# IDC_RS50_DIO_Sheet1.net
KiCad netlist of a schematic drawn in Altium Designer
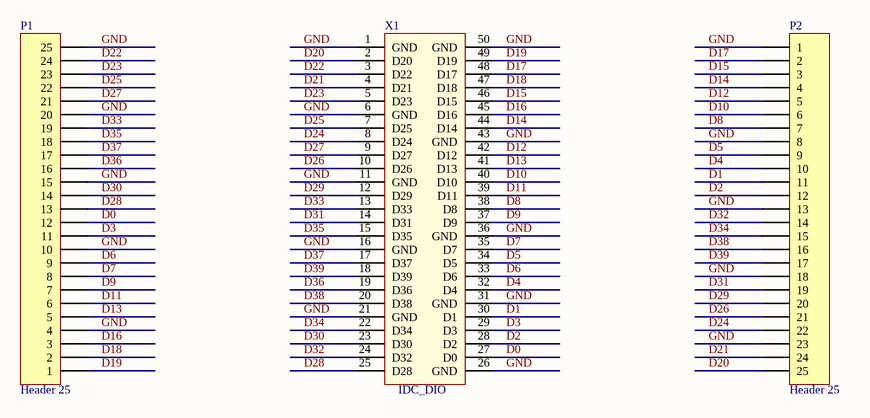
[diagram p0: IDC_RS50_DIO_Sheet1.SchDoc]

(export (version "E")
  (design (tool "Eeschema 10.0.6"))
  (components
    (comp (ref "P1")
      (value "Header 25")
      (footprint "HDR1X25")
      (description "Header, 25-Pin")
      (fields (field (name "PUBLISHER") "Altium Limited"))
      (libsource (lib "") (part "Header 25_1"))
    )
    (comp (ref "P2")
      (value "Header 25")
      (footprint "HDR1X25")
      (description "Header, 25-Pin")
      (fields (field (name "PUBLISHER") "Altium Limited"))
      (libsource (lib "Miscellaneous Connectors") (part "Header 25"))
    )
    (comp (ref "X1") (value "IDC_DIO") (footprint "IDC_DIO") (libsource (lib "VPL") (part "IDC_DIO")))
  )
  (nets
    (net (code "1") (name "/D0") (class "Default")
      (node (ref "P1") (pin "12") (pinfunction "12_12") (pintype "passive"))
      (node (ref "X1") (pin "27") (pinfunction "D0_27") (pintype "passive"))
    )
    (net (code "2") (name "/D1") (class "Default")
      (node (ref "P2") (pin "11") (pinfunction "11_11") (pintype "passive"))
      (node (ref "X1") (pin "30") (pinfunction "D1_30") (pintype "passive"))
    )
    (net (code "3") (name "/D2") (class "Default")
      (node (ref "P2") (pin "12") (pinfunction "12_12") (pintype "passive"))
      (node (ref "X1") (pin "28") (pinfunction "D2_28") (pintype "passive"))
    )
    (net (code "4") (name "/D3") (class "Default")
      (node (ref "P1") (pin "11") (pinfunction "11_11") (pintype "passive"))
      (node (ref "X1") (pin "29") (pinfunction "D3_29") (pintype "passive"))
    )
    (net (code "5") (name "/D4") (class "Default")
      (node (ref "P2") (pin "10") (pinfunction "10_10") (pintype "passive"))
      (node (ref "X1") (pin "32") (pinfunction "D4_32") (pintype "passive"))
    )
    (net (code "6") (name "/D5") (class "Default")
      (node (ref "P2") (pin "9") (pinfunction "9_9") (pintype "passive"))
      (node (ref "X1") (pin "34") (pinfunction "D5_34") (pintype "passive"))
    )
    (net (code "7") (name "/D6") (class "Default")
      (node (ref "P1") (pin "9") (pinfunction "9_9") (pintype "passive"))
      (node (ref "X1") (pin "33") (pinfunction "D6_33") (pintype "passive"))
    )
    (net (code "8") (name "/D7") (class "Default")
      (node (ref "P1") (pin "8") (pinfunction "8_8") (pintype "passive"))
      (node (ref "X1") (pin "35") (pinfunction "D7_35") (pintype "passive"))
    )
    (net (code "9") (name "/D8") (class "Default")
      (node (ref "P2") (pin "7") (pinfunction "7_7") (pintype "passive"))
      (node (ref "X1") (pin "38") (pinfunction "D8_38") (pintype "passive"))
    )
    (net (code "10") (name "/D9") (class "Default")
      (node (ref "P1") (pin "7") (pinfunction "7_7") (pintype "passive"))
      (node (ref "X1") (pin "37") (pinfunction "D9_37") (pintype "passive"))
    )
    (net (code "11") (name "/D10") (class "Default")
      (node (ref "P2") (pin "6") (pinfunction "6_6") (pintype "passive"))
      (node (ref "X1") (pin "40") (pinfunction "D10_40") (pintype "passive"))
    )
    (net (code "12") (name "/D11") (class "Default")
      (node (ref "P1") (pin "6") (pinfunction "6_6") (pintype "passive"))
      (node (ref "X1") (pin "39") (pinfunction "D11_39") (pintype "passive"))
    )
    (net (code "13") (name "/D12") (class "Default")
      (node (ref "P2") (pin "5") (pinfunction "5_5") (pintype "passive"))
      (node (ref "X1") (pin "42") (pinfunction "D12_42") (pintype "passive"))
    )
    (net (code "14") (name "/D13") (class "Default")
      (node (ref "P1") (pin "5") (pinfunction "5_5") (pintype "passive"))
      (node (ref "X1") (pin "41") (pinfunction "D13_41") (pintype "passive"))
    )
    (net (code "15") (name "/D14") (class "Default")
      (node (ref "P2") (pin "4") (pinfunction "4_4") (pintype "passive"))
      (node (ref "X1") (pin "44") (pinfunction "D14_44") (pintype "passive"))
    )
    (net (code "16") (name "/D15") (class "Default")
      (node (ref "P2") (pin "3") (pinfunction "3_3") (pintype "passive"))
      (node (ref "X1") (pin "46") (pinfunction "D15_46") (pintype "passive"))
    )
    (net (code "17") (name "/D16") (class "Default")
      (node (ref "P1") (pin "3") (pinfunction "3_3") (pintype "passive"))
      (node (ref "X1") (pin "45") (pinfunction "D16_45") (pintype "passive"))
    )
    (net (code "18") (name "/D17") (class "Default")
      (node (ref "P2") (pin "2") (pinfunction "2_2") (pintype "passive"))
      (node (ref "X1") (pin "48") (pinfunction "D17_48") (pintype "passive"))
    )
    (net (code "19") (name "/D18") (class "Default")
      (node (ref "P1") (pin "2") (pinfunction "2_2") (pintype "passive"))
      (node (ref "X1") (pin "47") (pinfunction "D18_47") (pintype "passive"))
    )
    (net (code "20") (name "/D19") (class "Default")
      (node (ref "P1") (pin "1") (pinfunction "1_1") (pintype "passive"))
      (node (ref "X1") (pin "49") (pinfunction "D19_49") (pintype "passive"))
    )
    (net (code "21") (name "/D20") (class "Default")
      (node (ref "P2") (pin "25") (pinfunction "25_25") (pintype "passive"))
      (node (ref "X1") (pin "2") (pinfunction "D20_2") (pintype "passive"))
    )
    (net (code "22") (name "/D21") (class "Default")
      (node (ref "P2") (pin "24") (pinfunction "24_24") (pintype "passive"))
      (node (ref "X1") (pin "4") (pinfunction "D21_4") (pintype "passive"))
    )
    (net (code "23") (name "/D22") (class "Default")
      (node (ref "P1") (pin "24") (pinfunction "24_24") (pintype "passive"))
      (node (ref "X1") (pin "3") (pinfunction "D22_3") (pintype "passive"))
    )
    (net (code "24") (name "/D23") (class "Default")
      (node (ref "P1") (pin "23") (pinfunction "23_23") (pintype "passive"))
      (node (ref "X1") (pin "5") (pinfunction "D23_5") (pintype "passive"))
    )
    (net (code "25") (name "/D24") (class "Default")
      (node (ref "P2") (pin "22") (pinfunction "22_22") (pintype "passive"))
      (node (ref "X1") (pin "8") (pinfunction "D24_8") (pintype "passive"))
    )
    (net (code "26") (name "/D25") (class "Default")
      (node (ref "P1") (pin "22") (pinfunction "22_22") (pintype "passive"))
      (node (ref "X1") (pin "7") (pinfunction "D25_7") (pintype "passive"))
    )
    (net (code "27") (name "/D26") (class "Default")
      (node (ref "P2") (pin "21") (pinfunction "21_21") (pintype "passive"))
      (node (ref "X1") (pin "10") (pinfunction "D26_10") (pintype "passive"))
    )
    (net (code "28") (name "/D27") (class "Default")
      (node (ref "P1") (pin "21") (pinfunction "21_21") (pintype "passive"))
      (node (ref "X1") (pin "9") (pinfunction "D27_9") (pintype "passive"))
    )
    (net (code "29") (name "/D28") (class "Default")
      (node (ref "P1") (pin "13") (pinfunction "13_13") (pintype "passive"))
      (node (ref "X1") (pin "25") (pinfunction "D28_25") (pintype "passive"))
    )
    (net (code "30") (name "/D29") (class "Default")
      (node (ref "P2") (pin "20") (pinfunction "20_20") (pintype "passive"))
      (node (ref "X1") (pin "12") (pinfunction "D29_12") (pintype "passive"))
    )
    (net (code "31") (name "/D30") (class "Default")
      (node (ref "P1") (pin "14") (pinfunction "14_14") (pintype "passive"))
      (node (ref "X1") (pin "23") (pinfunction "D30_23") (pintype "passive"))
    )
    (net (code "32") (name "/D31") (class "Default")
      (node (ref "P2") (pin "19") (pinfunction "19_19") (pintype "passive"))
      (node (ref "X1") (pin "14") (pinfunction "D31_14") (pintype "passive"))
    )
    (net (code "33") (name "/D32") (class "Default")
      (node (ref "P2") (pin "14") (pinfunction "14_14") (pintype "passive"))
      (node (ref "X1") (pin "24") (pinfunction "D32_24") (pintype "passive"))
    )
    (net (code "34") (name "/D33") (class "Default")
      (node (ref "P1") (pin "19") (pinfunction "19_19") (pintype "passive"))
      (node (ref "X1") (pin "13") (pinfunction "D33_13") (pintype "passive"))
    )
    (net (code "35") (name "/D34") (class "Default")
      (node (ref "P2") (pin "15") (pinfunction "15_15") (pintype "passive"))
      (node (ref "X1") (pin "22") (pinfunction "D34_22") (pintype "passive"))
    )
    (net (code "36") (name "/D35") (class "Default")
      (node (ref "P1") (pin "18") (pinfunction "18_18") (pintype "passive"))
      (node (ref "X1") (pin "15") (pinfunction "D35_15") (pintype "passive"))
    )
    (net (code "37") (name "/D36") (class "Default")
      (node (ref "P1") (pin "16") (pinfunction "16_16") (pintype "passive"))
      (node (ref "X1") (pin "19") (pinfunction "D36_19") (pintype "passive"))
    )
    (net (code "38") (name "/D37") (class "Default")
      (node (ref "P1") (pin "17") (pinfunction "17_17") (pintype "passive"))
      (node (ref "X1") (pin "17") (pinfunction "D37_17") (pintype "passive"))
    )
    (net (code "39") (name "/D38") (class "Default")
      (node (ref "P2") (pin "16") (pinfunction "16_16") (pintype "passive"))
      (node (ref "X1") (pin "20") (pinfunction "D38_20") (pintype "passive"))
    )
    (net (code "40") (name "/D39") (class "Default")
      (node (ref "P2") (pin "17") (pinfunction "17_17") (pintype "passive"))
      (node (ref "X1") (pin "18") (pinfunction "D39_18") (pintype "passive"))
    )
    (net (code "41") (name "/GND") (class "Default")
      (node (ref "P1") (pin "10") (pinfunction "10_10") (pintype "passive"))
      (node (ref "P1") (pin "15") (pinfunction "15_15") (pintype "passive"))
      (node (ref "P1") (pin "20") (pinfunction "20_20") (pintype "passive"))
      (node (ref "P1") (pin "25") (pinfunction "25_25") (pintype "passive"))
      (node (ref "P1") (pin "4") (pinfunction "4_4") (pintype "passive"))
      (node (ref "P2") (pin "1") (pinfunction "1_1") (pintype "passive"))
      (node (ref "P2") (pin "13") (pinfunction "13_13") (pintype "passive"))
      (node (ref "P2") (pin "18") (pinfunction "18_18") (pintype "passive"))
      (node (ref "P2") (pin "23") (pinfunction "23_23") (pintype "passive"))
      (node (ref "P2") (pin "8") (pinfunction "8_8") (pintype "passive"))
      (node (ref "X1") (pin "1") (pinfunction "GND_1") (pintype "passive"))
      (node (ref "X1") (pin "11") (pinfunction "GND_11") (pintype "passive"))
      (node (ref "X1") (pin "16") (pinfunction "GND_16") (pintype "passive"))
      (node (ref "X1") (pin "21") (pinfunction "GND_21") (pintype "passive"))
      (node (ref "X1") (pin "26") (pinfunction "GND_26") (pintype "passive"))
      (node (ref "X1") (pin "31") (pinfunction "GND_31") (pintype "passive"))
      (node (ref "X1") (pin "36") (pinfunction "GND_36") (pintype "passive"))
      (node (ref "X1") (pin "43") (pinfunction "GND_43") (pintype "passive"))
      (node (ref "X1") (pin "50") (pinfunction "GND_50") (pintype "passive"))
      (node (ref "X1") (pin "6") (pinfunction "GND_6") (pintype "passive"))
    )
  )
)
